# 1M_board.net
KiCad netlist of a schematic drawn in EAGLE
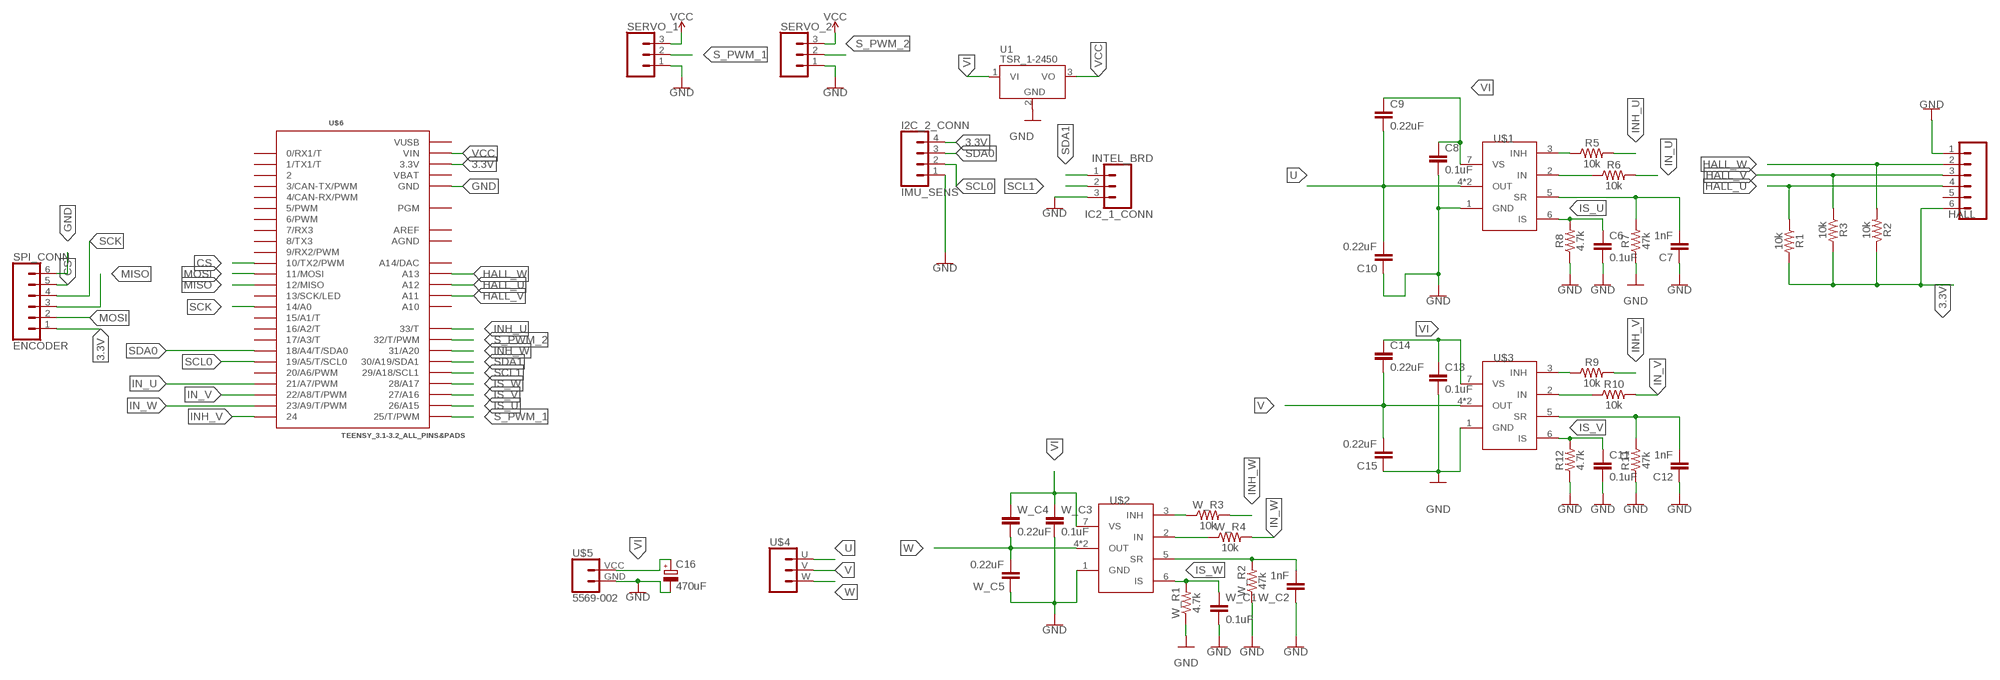
[diagram p0: schematic, sheet 1]

(export (version "E")
  (design (tool "Eeschema 10.0.6"))
  (components
    (comp (ref "C6")
      (value "0.1uF")
      (footprint "eagle-import:0603")
      (libsource (lib "eagle-import") (part "0.1UF-0603-25V-5%"))
    )
    (comp (ref "C7")
      (value "1nF")
      (footprint "eagle-import:0603")
      (libsource (lib "eagle-import") (part "1.0NF/1000PF-0603-50V-10%"))
    )
    (comp (ref "C8")
      (value "0.1uF")
      (footprint "eagle-import:0603")
      (libsource (lib "eagle-import") (part "0.1UF-0603-25V-5%"))
    )
    (comp (ref "C9")
      (value "0.22uF")
      (footprint "eagle-import:0603")
      (libsource (lib "eagle-import") (part "0.22UF-0603-25V-10%"))
    )
    (comp (ref "C10")
      (value "0.22uF")
      (footprint "eagle-import:0603")
      (libsource (lib "eagle-import") (part "0.22UF-0603-25V-10%"))
    )
    (comp (ref "C11")
      (value "0.1uF")
      (footprint "eagle-import:0603")
      (libsource (lib "eagle-import") (part "0.1UF-0603-25V-5%"))
    )
    (comp (ref "C12")
      (value "1nF")
      (footprint "eagle-import:0603")
      (libsource (lib "eagle-import") (part "1.0NF/1000PF-0603-50V-10%"))
    )
    (comp (ref "C13")
      (value "0.1uF")
      (footprint "eagle-import:0603")
      (libsource (lib "eagle-import") (part "0.1UF-0603-25V-5%"))
    )
    (comp (ref "C14")
      (value "0.22uF")
      (footprint "eagle-import:0603")
      (libsource (lib "eagle-import") (part "0.22UF-0603-25V-10%"))
    )
    (comp (ref "C15")
      (value "0.22uF")
      (footprint "eagle-import:0603")
      (libsource (lib "eagle-import") (part "0.22UF-0603-25V-10%"))
    )
    (comp (ref "C16")
      (value "470uF")
      (footprint "eagle-import:E2,5-6E")
      (libsource (lib "eagle-import") (part "CPOL-EUE2,5-6E"))
    )
    (comp (ref "HALL")
      (value "CONN_06SMD-1MM")
      (footprint "eagle-import:1X06-1MM")
      (libsource (lib "eagle-import") (part "CONN_06SMD-1MM"))
    )
    (comp (ref "I2C_2_CONN")
      (value "IMU_SENS")
      (footprint "eagle-import:1X04_NO_SILK")
      (libsource (lib "eagle-import") (part "CONN_041X04_NO_SILK"))
    )
    (comp (ref "IC2_1_CONN")
      (value "INTEL_BRD")
      (footprint "eagle-import:1X03_NO_SILK")
      (libsource (lib "eagle-import") (part "CONN_031X03_NO_SILK"))
    )
    (comp (ref "R1")
      (value "10k")
      (footprint "eagle-import:0603")
      (libsource (lib "eagle-import") (part "10KOHM-0603-1/10W-1%"))
    )
    (comp (ref "R2")
      (value "10k")
      (footprint "eagle-import:0603")
      (libsource (lib "eagle-import") (part "10KOHM-0603-1/10W-1%"))
    )
    (comp (ref "R3")
      (value "10k")
      (footprint "eagle-import:0603")
      (libsource (lib "eagle-import") (part "10KOHM-0603-1/10W-1%"))
    )
    (comp (ref "R5")
      (value "10k")
      (footprint "eagle-import:0603")
      (libsource (lib "eagle-import") (part "10KOHM-0603-1/10W-1%"))
    )
    (comp (ref "R6")
      (value "10k")
      (footprint "eagle-import:0603")
      (libsource (lib "eagle-import") (part "10KOHM-0603-1/10W-1%"))
    )
    (comp (ref "R7")
      (value "47k")
      (footprint "eagle-import:0603")
      (libsource (lib "eagle-import") (part "47KOHM-0603-1/10W-1%"))
    )
    (comp (ref "R8")
      (value "4.7k")
      (footprint "eagle-import:0603")
      (libsource (lib "eagle-import") (part "4.7KOHM-0603-1/10W-1%"))
    )
    (comp (ref "R9")
      (value "10k")
      (footprint "eagle-import:0603")
      (libsource (lib "eagle-import") (part "10KOHM-0603-1/10W-1%"))
    )
    (comp (ref "R10")
      (value "10k")
      (footprint "eagle-import:0603")
      (libsource (lib "eagle-import") (part "10KOHM-0603-1/10W-1%"))
    )
    (comp (ref "R11")
      (value "47k")
      (footprint "eagle-import:0603")
      (libsource (lib "eagle-import") (part "47KOHM-0603-1/10W-1%"))
    )
    (comp (ref "R12")
      (value "4.7k")
      (footprint "eagle-import:0603")
      (libsource (lib "eagle-import") (part "4.7KOHM-0603-1/10W-1%"))
    )
    (comp (ref "SERVO_1")
      (value "CONN_031X03_NO_SILK")
      (footprint "eagle-import:1X03_NO_SILK")
      (libsource (lib "eagle-import") (part "CONN_031X03_NO_SILK"))
    )
    (comp (ref "SERVO_2")
      (value "CONN_031X03_NO_SILK")
      (footprint "eagle-import:1X03_NO_SILK")
      (libsource (lib "eagle-import") (part "CONN_031X03_NO_SILK"))
    )
    (comp (ref "SPI_CONN")
      (value "ENCODER")
      (footprint "eagle-import:1X06-1MM")
      (libsource (lib "eagle-import") (part "CONN_06SMD-1MM"))
    )
    (comp (ref "U$1")
      (value "IFX007TZZZZ")
      (footprint "eagle-import:P-TO263-7-1")
      (libsource (lib "eagle-import") (part "IFX007TZZZZ"))
    )
    (comp (ref "U$2")
      (value "IFX007TZZZZ")
      (footprint "eagle-import:P-TO263-7-1")
      (libsource (lib "eagle-import") (part "IFX007TZZZZ"))
    )
    (comp (ref "U$3")
      (value "IFX007TZZZZ")
      (footprint "eagle-import:P-TO263-7-1")
      (libsource (lib "eagle-import") (part "IFX007TZZZZ"))
    )
    (comp (ref "U$4")
      (value "5569-003")
      (footprint "eagle-import:5569-003")
      (libsource (lib "eagle-import") (part "5569-003"))
    )
    (comp (ref "U$5")
      (value "5569-002")
      (footprint "eagle-import:5569-002")
      (libsource (lib "eagle-import") (part "5569-002"))
    )
    (comp (ref "U$6")
      (value "TEENSY_3.1-3.2_ALL_PINS&PADS")
      (footprint "eagle-import:TEENSY_3.0-3.2_ALL_PINS_&_PADS")
      (libsource (lib "eagle-import") (part "TEENSY_3.1-3.2_ALL_PINS&PADS"))
    )
    (comp (ref "U1")
      (value "TSR_1-2450")
      (footprint "eagle-import:TSR-1")
      (libsource (lib "eagle-import") (part "TSR_1-2450"))
    )
    (comp (ref "W_C1")
      (value "0.1uF")
      (footprint "eagle-import:0603")
      (libsource (lib "eagle-import") (part "0.1UF-0603-25V-5%"))
    )
    (comp (ref "W_C2")
      (value "1nF")
      (footprint "eagle-import:0603")
      (libsource (lib "eagle-import") (part "1.0NF/1000PF-0603-50V-10%"))
    )
    (comp (ref "W_C3")
      (value "0.1uF")
      (footprint "eagle-import:0603")
      (libsource (lib "eagle-import") (part "0.1UF-0603-25V-5%"))
    )
    (comp (ref "W_C4")
      (value "0.22uF")
      (footprint "eagle-import:0603")
      (libsource (lib "eagle-import") (part "0.22UF-0603-25V-10%"))
    )
    (comp (ref "W_C5")
      (value "0.22uF")
      (footprint "eagle-import:0603")
      (libsource (lib "eagle-import") (part "0.22UF-0603-25V-10%"))
    )
    (comp (ref "W_R1")
      (value "4.7k")
      (footprint "eagle-import:0603")
      (libsource (lib "eagle-import") (part "4.7KOHM-0603-1/10W-1%"))
    )
    (comp (ref "W_R2")
      (value "47k")
      (footprint "eagle-import:0603")
      (libsource (lib "eagle-import") (part "47KOHM-0603-1/10W-1%"))
    )
    (comp (ref "W_R3")
      (value "10k")
      (footprint "eagle-import:0603")
      (libsource (lib "eagle-import") (part "10KOHM-0603-1/10W-1%"))
    )
    (comp (ref "W_R4")
      (value "10k")
      (footprint "eagle-import:0603")
      (libsource (lib "eagle-import") (part "10KOHM-0603-1/10W-1%"))
    )
  )
  (nets
    (net (code "1") (name "/AGND") (class "Default")
      (node (ref "U$6") (pin "AGND") (pinfunction "AGND_AGND") (pintype "power_in"))
    )
    (net (code "2") (name "/AREF") (class "Default")
      (node (ref "U$6") (pin "AREF") (pinfunction "AREF_AREF") (pintype "power_in"))
    )
    (net (code "3") (name "/VBAT") (class "Default")
      (node (ref "U$6") (pin "VBAT") (pinfunction "VBAT_VBAT") (pintype "power_in"))
    )
    (net (code "4") (name "/VUSB") (class "Default")
      (node (ref "U$6") (pin "VUSB") (pinfunction "VUSB_VUSB") (pintype "power_in"))
    )
    (net (code "5") (name "3.3V") (class "Default")
      (node (ref "HALL") (pin "6") (pinfunction "6_6") (pintype "passive"))
      (node (ref "I2C_2_CONN") (pin "4") (pinfunction "4_4") (pintype "passive"))
      (node (ref "R1") (pin "2") (pinfunction "2_2") (pintype "passive"))
      (node (ref "R2") (pin "1") (pinfunction "1_1") (pintype "passive"))
      (node (ref "R3") (pin "2") (pinfunction "2_2") (pintype "passive"))
      (node (ref "SPI_CONN") (pin "1") (pinfunction "1_1") (pintype "passive"))
      (node (ref "U$6") (pin "3.3V") (pinfunction "3.3V_3.3V") (pintype "power_in"))
      (node (ref "U$6") (pin "3.3V1") (pinfunction "3.3V_3.3V1") (pintype "power_in"))
      (node (ref "U$6") (pin "3.3V2") (pinfunction "3.3V_3.3V2") (pintype "power_in"))
    )
    (net (code "6") (name "CS") (class "Default")
      (node (ref "SPI_CONN") (pin "5") (pinfunction "5_5") (pintype "passive"))
      (node (ref "U$6") (pin "10") (pinfunction "10/TX2/PWM_10") (pintype "bidirectional"))
    )
    (net (code "7") (name "GND") (class "Default")
      (node (ref "C10") (pin "1") (pinfunction "1_1") (pintype "passive"))
      (node (ref "C11") (pin "2") (pinfunction "2_2") (pintype "passive"))
      (node (ref "C12") (pin "1") (pinfunction "1_1") (pintype "passive"))
      (node (ref "C13") (pin "2") (pinfunction "2_2") (pintype "passive"))
      (node (ref "C15") (pin "1") (pinfunction "1_1") (pintype "passive"))
      (node (ref "C16") (pin "-") (pinfunction "-_-") (pintype "passive"))
      (node (ref "C6") (pin "2") (pinfunction "2_2") (pintype "passive"))
      (node (ref "C7") (pin "1") (pinfunction "1_1") (pintype "passive"))
      (node (ref "C8") (pin "2") (pinfunction "2_2") (pintype "passive"))
      (node (ref "HALL") (pin "1") (pinfunction "1_1") (pintype "passive"))
      (node (ref "I2C_2_CONN") (pin "1") (pinfunction "1_1") (pintype "passive"))
      (node (ref "IC2_1_CONN") (pin "3") (pinfunction "3_3") (pintype "passive"))
      (node (ref "R11") (pin "1") (pinfunction "1_1") (pintype "passive"))
      (node (ref "R12") (pin "1") (pinfunction "1_1") (pintype "passive"))
      (node (ref "R7") (pin "1") (pinfunction "1_1") (pintype "passive"))
      (node (ref "R8") (pin "1") (pinfunction "1_1") (pintype "passive"))
      (node (ref "SERVO_1") (pin "1") (pinfunction "1_1") (pintype "passive"))
      (node (ref "SERVO_2") (pin "1") (pinfunction "1_1") (pintype "passive"))
      (node (ref "SPI_CONN") (pin "6") (pinfunction "6_6") (pintype "passive"))
      (node (ref "U$1") (pin "1") (pinfunction "GND_1") (pintype "power_in"))
      (node (ref "U$2") (pin "1") (pinfunction "GND_1") (pintype "power_in"))
      (node (ref "U$3") (pin "1") (pinfunction "GND_1") (pintype "power_in"))
      (node (ref "U$5") (pin "GND") (pinfunction "1_GND") (pintype "passive"))
      (node (ref "U$6") (pin "GND") (pinfunction "GND_GND") (pintype "power_in"))
      (node (ref "U$6") (pin "GND1") (pinfunction "GND_GND1") (pintype "power_in"))
      (node (ref "U$6") (pin "GND2") (pinfunction "GND_GND2") (pintype "power_in"))
      (node (ref "U1") (pin "2") (pinfunction "GND_2") (pintype "power_in"))
      (node (ref "W_C1") (pin "2") (pinfunction "2_2") (pintype "passive"))
      (node (ref "W_C2") (pin "1") (pinfunction "1_1") (pintype "passive"))
      (node (ref "W_C3") (pin "2") (pinfunction "2_2") (pintype "passive"))
      (node (ref "W_C5") (pin "1") (pinfunction "1_1") (pintype "passive"))
      (node (ref "W_R1") (pin "1") (pinfunction "1_1") (pintype "passive"))
      (node (ref "W_R2") (pin "1") (pinfunction "1_1") (pintype "passive"))
    )
    (net (code "8") (name "HALL_U") (class "Default")
      (node (ref "HALL") (pin "4") (pinfunction "4_4") (pintype "passive"))
      (node (ref "R1") (pin "1") (pinfunction "1_1") (pintype "passive"))
      (node (ref "U$6") (pin "A12") (pinfunction "A12_A12") (pintype "bidirectional"))
    )
    (net (code "9") (name "HALL_V") (class "Default")
      (node (ref "HALL") (pin "3") (pinfunction "3_3") (pintype "passive"))
      (node (ref "R3") (pin "1") (pinfunction "1_1") (pintype "passive"))
      (node (ref "U$6") (pin "A11") (pinfunction "A11_A11") (pintype "bidirectional"))
    )
    (net (code "10") (name "HALL_W") (class "Default")
      (node (ref "HALL") (pin "2") (pinfunction "2_2") (pintype "passive"))
      (node (ref "R2") (pin "2") (pinfunction "2_2") (pintype "passive"))
      (node (ref "U$6") (pin "A13") (pinfunction "A13_A13") (pintype "bidirectional"))
    )
    (net (code "11") (name "INH_U") (class "Default")
      (node (ref "R5") (pin "2") (pinfunction "2_2") (pintype "passive"))
      (node (ref "U$6") (pin "33") (pinfunction "33/T_33") (pintype "bidirectional"))
    )
    (net (code "12") (name "INH_V") (class "Default")
      (node (ref "R9") (pin "2") (pinfunction "2_2") (pintype "passive"))
      (node (ref "U$6") (pin "24") (pinfunction "24_24") (pintype "bidirectional"))
    )
    (net (code "13") (name "INH_W") (class "Default")
      (node (ref "U$6") (pin "31") (pinfunction "31/A20_31") (pintype "bidirectional"))
      (node (ref "W_R3") (pin "2") (pinfunction "2_2") (pintype "passive"))
    )
    (net (code "14") (name "IN_U") (class "Default")
      (node (ref "R6") (pin "2") (pinfunction "2_2") (pintype "passive"))
      (node (ref "U$6") (pin "21/A7") (pinfunction "21/A7/PWM_21/A7") (pintype "bidirectional"))
    )
    (net (code "15") (name "IN_V") (class "Default")
      (node (ref "R10") (pin "2") (pinfunction "2_2") (pintype "passive"))
      (node (ref "U$6") (pin "22/A8") (pinfunction "22/A8/T/PWM_22/A8") (pintype "bidirectional"))
    )
    (net (code "16") (name "IN_W") (class "Default")
      (node (ref "U$6") (pin "23/A9") (pinfunction "23/A9/T/PWM_23/A9") (pintype "bidirectional"))
      (node (ref "W_R4") (pin "2") (pinfunction "2_2") (pintype "passive"))
    )
    (net (code "17") (name "IS_U") (class "Default")
      (node (ref "C6") (pin "1") (pinfunction "1_1") (pintype "passive"))
      (node (ref "R8") (pin "2") (pinfunction "2_2") (pintype "passive"))
      (node (ref "U$1") (pin "6") (pinfunction "IS_6") (pintype "output"))
      (node (ref "U$6") (pin "26") (pinfunction "26/A15_26") (pintype "bidirectional"))
    )
    (net (code "18") (name "IS_V") (class "Default")
      (node (ref "C11") (pin "1") (pinfunction "1_1") (pintype "passive"))
      (node (ref "R12") (pin "2") (pinfunction "2_2") (pintype "passive"))
      (node (ref "U$3") (pin "6") (pinfunction "IS_6") (pintype "output"))
      (node (ref "U$6") (pin "27") (pinfunction "27/A16_27") (pintype "bidirectional"))
    )
    (net (code "19") (name "IS_W") (class "Default")
      (node (ref "U$2") (pin "6") (pinfunction "IS_6") (pintype "output"))
      (node (ref "U$6") (pin "28") (pinfunction "28/A17_28") (pintype "bidirectional"))
      (node (ref "W_C1") (pin "1") (pinfunction "1_1") (pintype "passive"))
      (node (ref "W_R1") (pin "2") (pinfunction "2_2") (pintype "passive"))
    )
    (net (code "20") (name "MISO") (class "Default")
      (node (ref "SPI_CONN") (pin "3") (pinfunction "3_3") (pintype "passive"))
      (node (ref "U$6") (pin "12") (pinfunction "12/MISO_12") (pintype "bidirectional"))
    )
    (net (code "21") (name "MOSI") (class "Default")
      (node (ref "SPI_CONN") (pin "2") (pinfunction "2_2") (pintype "passive"))
      (node (ref "U$6") (pin "11") (pinfunction "11/MOSI_11") (pintype "bidirectional"))
    )
    (net (code "22") (name "Net-(U$1-IN)") (class "Default")
      (node (ref "R6") (pin "1") (pinfunction "1_1") (pintype "passive"))
      (node (ref "U$1") (pin "2") (pinfunction "IN_2") (pintype "input"))
    )
    (net (code "23") (name "Net-(U$1-INH)") (class "Default")
      (node (ref "R5") (pin "1") (pinfunction "1_1") (pintype "passive"))
      (node (ref "U$1") (pin "3") (pinfunction "INH_3") (pintype "bidirectional"))
    )
    (net (code "24") (name "Net-(U$1-SR)") (class "Default")
      (node (ref "C7") (pin "2") (pinfunction "2_2") (pintype "passive"))
      (node (ref "R7") (pin "2") (pinfunction "2_2") (pintype "passive"))
      (node (ref "U$1") (pin "5") (pinfunction "SR_5") (pintype "input"))
    )
    (net (code "25") (name "Net-(U$2-IN)") (class "Default")
      (node (ref "U$2") (pin "2") (pinfunction "IN_2") (pintype "input"))
      (node (ref "W_R4") (pin "1") (pinfunction "1_1") (pintype "passive"))
    )
    (net (code "26") (name "Net-(U$2-INH)") (class "Default")
      (node (ref "U$2") (pin "3") (pinfunction "INH_3") (pintype "bidirectional"))
      (node (ref "W_R3") (pin "1") (pinfunction "1_1") (pintype "passive"))
    )
    (net (code "27") (name "Net-(U$2-SR)") (class "Default")
      (node (ref "U$2") (pin "5") (pinfunction "SR_5") (pintype "input"))
      (node (ref "W_C2") (pin "2") (pinfunction "2_2") (pintype "passive"))
      (node (ref "W_R2") (pin "2") (pinfunction "2_2") (pintype "passive"))
    )
    (net (code "28") (name "Net-(U$3-IN)") (class "Default")
      (node (ref "R10") (pin "1") (pinfunction "1_1") (pintype "passive"))
      (node (ref "U$3") (pin "2") (pinfunction "IN_2") (pintype "input"))
    )
    (net (code "29") (name "Net-(U$3-INH)") (class "Default")
      (node (ref "R9") (pin "1") (pinfunction "1_1") (pintype "passive"))
      (node (ref "U$3") (pin "3") (pinfunction "INH_3") (pintype "bidirectional"))
    )
    (net (code "30") (name "Net-(U$3-SR)") (class "Default")
      (node (ref "C12") (pin "2") (pinfunction "2_2") (pintype "passive"))
      (node (ref "R11") (pin "2") (pinfunction "2_2") (pintype "passive"))
      (node (ref "U$3") (pin "5") (pinfunction "SR_5") (pintype "input"))
    )
    (net (code "31") (name "SCK") (class "Default")
      (node (ref "SPI_CONN") (pin "4") (pinfunction "4_4") (pintype "passive"))
      (node (ref "U$6") (pin "14/A0") (pinfunction "14/A0_14/A0") (pintype "bidirectional"))
    )
    (net (code "32") (name "SCL0") (class "Default")
      (node (ref "I2C_2_CONN") (pin "2") (pinfunction "2_2") (pintype "passive"))
      (node (ref "U$6") (pin "19/A5") (pinfunction "19/A5/T/SCL0_19/A5") (pintype "bidirectional"))
    )
    (net (code "33") (name "SCL1") (class "Default")
      (node (ref "IC2_1_CONN") (pin "2") (pinfunction "2_2") (pintype "passive"))
      (node (ref "U$6") (pin "29") (pinfunction "29/A18/SCL1_29") (pintype "bidirectional"))
    )
    (net (code "34") (name "SDA0") (class "Default")
      (node (ref "I2C_2_CONN") (pin "3") (pinfunction "3_3") (pintype "passive"))
      (node (ref "U$6") (pin "18/A4") (pinfunction "18/A4/T/SDA0_18/A4") (pintype "bidirectional"))
    )
    (net (code "35") (name "SDA1") (class "Default")
      (node (ref "IC2_1_CONN") (pin "1") (pinfunction "1_1") (pintype "passive"))
      (node (ref "U$6") (pin "30") (pinfunction "30/A19/SDA1_30") (pintype "bidirectional"))
    )
    (net (code "36") (name "S_PWM_1") (class "Default")
      (node (ref "SERVO_1") (pin "2") (pinfunction "2_2") (pintype "passive"))
      (node (ref "U$6") (pin "25") (pinfunction "25/T/PWM_25") (pintype "bidirectional"))
    )
    (net (code "37") (name "S_PWM_2") (class "Default")
      (node (ref "SERVO_2") (pin "2") (pinfunction "2_2") (pintype "passive"))
      (node (ref "U$6") (pin "32") (pinfunction "32/T/PWM_32") (pintype "bidirectional"))
    )
    (net (code "38") (name "U") (class "Default")
      (node (ref "C10") (pin "2") (pinfunction "2_2") (pintype "passive"))
      (node (ref "C9") (pin "2") (pinfunction "2_2") (pintype "passive"))
      (node (ref "U$1") (pin "4") (pinfunction "OUT_4") (pintype "power_in"))
      (node (ref "U$1") (pin "8") (pinfunction "OUT_8") (pintype "power_in"))
      (node (ref "U$4") (pin "U") (pinfunction "W_U") (pintype "passive"))
    )
    (net (code "39") (name "V") (class "Default")
      (node (ref "C14") (pin "2") (pinfunction "2_2") (pintype "passive"))
      (node (ref "C15") (pin "2") (pinfunction "2_2") (pintype "passive"))
      (node (ref "U$3") (pin "4") (pinfunction "OUT_4") (pintype "power_in"))
      (node (ref "U$3") (pin "8") (pinfunction "OUT_8") (pintype "power_in"))
      (node (ref "U$4") (pin "V") (pinfunction "U_V") (pintype "passive"))
    )
    (net (code "40") (name "VCC") (class "Default")
      (node (ref "SERVO_1") (pin "3") (pinfunction "3_3") (pintype "passive"))
      (node (ref "SERVO_2") (pin "3") (pinfunction "3_3") (pintype "passive"))
      (node (ref "U$6") (pin "VIN") (pinfunction "VIN_VIN") (pintype "power_in"))
      (node (ref "U1") (pin "3") (pinfunction "VO_3") (pintype "power_in"))
    )
    (net (code "41") (name "VI") (class "Default")
      (node (ref "C13") (pin "1") (pinfunction "1_1") (pintype "passive"))
      (node (ref "C14") (pin "1") (pinfunction "1_1") (pintype "passive"))
      (node (ref "C16") (pin "+") (pinfunction "+_+") (pintype "passive"))
      (node (ref "C8") (pin "1") (pinfunction "1_1") (pintype "passive"))
      (node (ref "C9") (pin "1") (pinfunction "1_1") (pintype "passive"))
      (node (ref "U$1") (pin "7") (pinfunction "VS_7") (pintype "power_in"))
      (node (ref "U$2") (pin "7") (pinfunction "VS_7") (pintype "power_in"))
      (node (ref "U$3") (pin "7") (pinfunction "VS_7") (pintype "power_in"))
      (node (ref "U$5") (pin "VCC") (pinfunction "2_VCC") (pintype "passive"))
      (node (ref "U1") (pin "1") (pinfunction "VI_1") (pintype "power_in"))
      (node (ref "W_C3") (pin "1") (pinfunction "1_1") (pintype "passive"))
      (node (ref "W_C4") (pin "1") (pinfunction "1_1") (pintype "passive"))
    )
    (net (code "42") (name "W") (class "Default")
      (node (ref "U$2") (pin "4") (pinfunction "OUT_4") (pintype "power_in"))
      (node (ref "U$2") (pin "8") (pinfunction "OUT_8") (pintype "power_in"))
      (node (ref "U$4") (pin "W") (pinfunction "V_W") (pintype "passive"))
      (node (ref "W_C4") (pin "2") (pinfunction "2_2") (pintype "passive"))
      (node (ref "W_C5") (pin "2") (pinfunction "2_2") (pintype "passive"))
    )
    (net (code "43") (name "unconnected-(HALL-Pad5)") (class "Default")
      (node (ref "HALL") (pin "5") (pinfunction "5_5") (pintype "passive"))
    )
    (net (code "44") (name "unconnected-(U$6-0{slash}RX1{slash}T-Pad0)") (class "Default")
      (node (ref "U$6") (pin "0") (pinfunction "0/RX1/T_0") (pintype "bidirectional"))
    )
    (net (code "45") (name "unconnected-(U$6-1{slash}TX1{slash}T-Pad1)") (class "Default")
      (node (ref "U$6") (pin "1") (pinfunction "1/TX1/T_1") (pintype "bidirectional"))
    )
    (net (code "46") (name "unconnected-(U$6-3{slash}CAN-TX{slash}PWM-Pad3)") (class "Default")
      (node (ref "U$6") (pin "3") (pinfunction "3/CAN-TX/PWM_3") (pintype "bidirectional"))
    )
    (net (code "47") (name "unconnected-(U$6-4{slash}CAN-RX{slash}PWM-Pad4)") (class "Default")
      (node (ref "U$6") (pin "4") (pinfunction "4/CAN-RX/PWM_4") (pintype "bidirectional"))
    )
    (net (code "48") (name "unconnected-(U$6-5{slash}PWM-Pad5)") (class "Default")
      (node (ref "U$6") (pin "5") (pinfunction "5/PWM_5") (pintype "bidirectional"))
    )
    (net (code "49") (name "unconnected-(U$6-6{slash}PWM-Pad6)") (class "Default")
      (node (ref "U$6") (pin "6") (pinfunction "6/PWM_6") (pintype "bidirectional"))
    )
    (net (code "50") (name "unconnected-(U$6-7{slash}RX3-Pad7)") (class "Default")
      (node (ref "U$6") (pin "7") (pinfunction "7/RX3_7") (pintype "bidirectional"))
    )
    (net (code "51") (name "unconnected-(U$6-8{slash}TX3-Pad8)") (class "Default")
      (node (ref "U$6") (pin "8") (pinfunction "8/TX3_8") (pintype "bidirectional"))
    )
    (net (code "52") (name "unconnected-(U$6-9{slash}RX2{slash}PWM-Pad9)") (class "Default")
      (node (ref "U$6") (pin "9") (pinfunction "9/RX2/PWM_9") (pintype "bidirectional"))
    )
    (net (code "53") (name "unconnected-(U$6-13{slash}SCK{slash}LED-Pad13)") (class "Default")
      (node (ref "U$6") (pin "13") (pinfunction "13/SCK/LED_13") (pintype "bidirectional"))
    )
    (net (code "54") (name "unconnected-(U$6-15{slash}A1{slash}T-Pad15{slash}A1)") (class "Default")
      (node (ref "U$6") (pin "15/A1") (pinfunction "15/A1/T_15/A1") (pintype "bidirectional"))
    )
    (net (code "55") (name "unconnected-(U$6-16{slash}A2{slash}T-Pad16{slash}A2)") (class "Default")
      (node (ref "U$6") (pin "16/A2") (pinfunction "16/A2/T_16/A2") (pintype "bidirectional"))
    )
    (net (code "56") (name "unconnected-(U$6-17{slash}A3{slash}T-Pad17{slash}A3)") (class "Default")
      (node (ref "U$6") (pin "17/A3") (pinfunction "17/A3/T_17/A3") (pintype "bidirectional"))
    )
    (net (code "57") (name "unconnected-(U$6-20{slash}A6{slash}PWM-Pad20{slash}A6)") (class "Default")
      (node (ref "U$6") (pin "20/A6") (pinfunction "20/A6/PWM_20/A6") (pintype "bidirectional"))
    )
    (net (code "58") (name "unconnected-(U$6-A14{slash}DAC-PadRESET{slash}DAC)") (class "Default")
      (node (ref "U$6") (pin "RESET/DAC") (pinfunction "A14/DAC_RESET/DAC") (pintype "bidirectional"))
    )
    (net (code "59") (name "unconnected-(U$6-Pad2)") (class "Default")
      (node (ref "U$6") (pin "2") (pinfunction "2_2") (pintype "bidirectional"))
    )
    (net (code "60") (name "unconnected-(U$6-PadA10)") (class "Default")
      (node (ref "U$6") (pin "A10") (pinfunction "A10_A10") (pintype "bidirectional"))
    )
    (net (code "61") (name "unconnected-(U$6-PadPGM)") (class "Default")
      (node (ref "U$6") (pin "PGM") (pinfunction "PGM_PGM") (pintype "bidirectional"))
    )
  )
)
